# Charger.net
KiCad netlist of a schematic drawn in Altium Designer
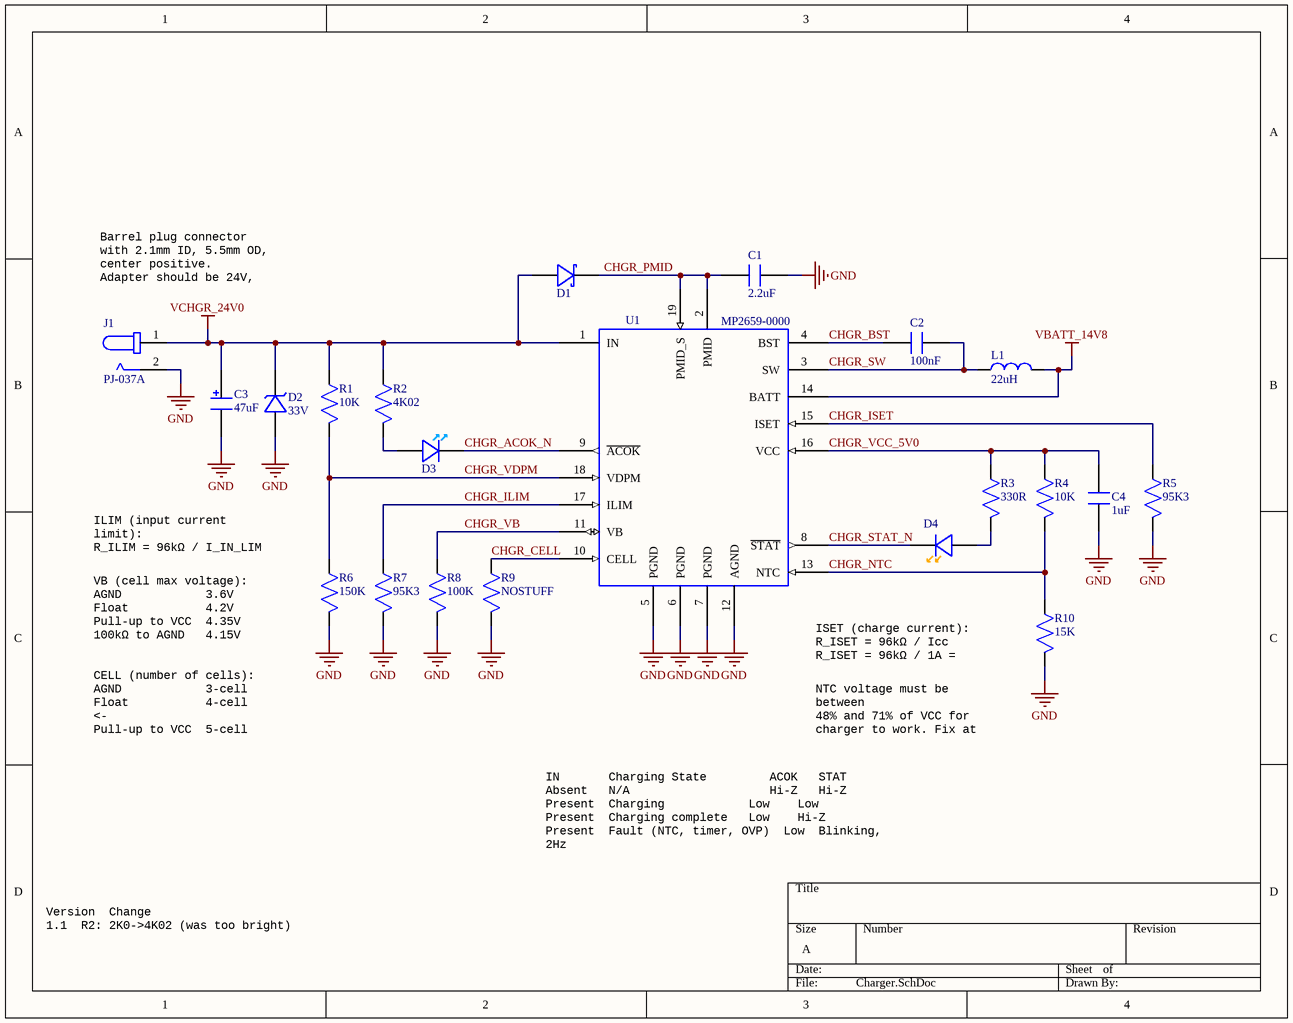
[diagram p0: Charger.SchDoc]

(export (version "E")
  (design (tool "Eeschema 10.0.6"))
  (components
    (comp (ref "C1")
      (value "~")
      (footprint "1206_CAP")
      (fields
        (field (name "MANUFACTURER") "Samsung Electro-Mechanics")
        (field (name "PART NUMBER") "CL31B225KBHNFNE")
        (field (name "TOLERANCE") "10%")
        (field (name "CAPACITANCE") "2.2uF")
      )
      (libsource (lib "SharedPartsLib") (part "CAP_1206_2.2uF"))
    )
    (comp (ref "C2")
      (value "~")
      (footprint "0603_CAP")
      (fields
        (field (name "MANUFACTURER") "Samsung Electro-Mechanics")
        (field (name "PART NUMBER") "CL10B104KB8NNWC")
        (field (name "TOLERANCE") "10%")
        (field (name "CAPACITANCE") "100nF")
      )
      (libsource (lib "SharedPartsLib") (part "CAP_0603_100nF"))
    )
    (comp (ref "C3")
      (value "~")
      (footprint "CAP_RADIAL_5MMx11MM")
      (fields
        (field (name "MANUFACTURER") "Würth Elektronik")
        (field (name "PART NUMBER") "860020572006")
        (field (name "TOLERANCE") "20%")
        (field (name "CAPACITANCE") "47uF")
      )
      (libsource (lib "SharedPartsLib") (part "CAP_RADIAL_47uF"))
    )
    (comp (ref "C4")
      (value "~")
      (footprint "0603_CAP")
      (fields
        (field (name "MANUFACTURER") "Samsung Electro-Mechanics")
        (field (name "PART NUMBER") "CL10B105KA8NNNC")
        (field (name "TOLERANCE") "10%")
        (field (name "CAPACITANCE") "1uF")
      )
      (libsource (lib "SharedPartsLib") (part "CAP_0603_1uF"))
    )
    (comp (ref "D1")
      (value "*")
      (footprint "DO-214AC_SMA")
      (fields (field (name "MANUFACTURER") "Diodes Incorporated") (field (name "PART NUMBER") "B240AE-13"))
      (libsource (lib "SharedPartsLib") (part "DIODE_SCHOTTKY_40V_2A"))
    )
    (comp (ref "D2")
      (value "*")
      (footprint "DO-214AC_SMA")
      (fields
        (field (name "MANUFACTURER") "Diodes Incorporated")
        (field (name "PART NUMBER") "SMAJ33AQ-13-F")
        (field (name "REVERSE STANDOFF VOLTAGE") "33V")
      )
      (libsource (lib "SharedPartsLib") (part "DIODE_TVS_33V_UNIDIR"))
    )
    (comp (ref "D3")
      (value "*")
      (footprint "LED_1411")
      (fields (field (name "MANUFACTURER") "Würth Elektronik") (field (name "PART NUMBER") "150141BS73100"))
      (libsource (lib "SharedPartsLib") (part "LED_BLUE_150141BS73100"))
    )
    (comp (ref "D4")
      (value "*")
      (footprint "LED_1411")
      (fields (field (name "MANUFACTURER") "Würth Elektronik") (field (name "PART NUMBER") "150141AS73100"))
      (libsource (lib "SharedPartsLib") (part "LED_AMBER_150141AS73100"))
    )
    (comp (ref "J1")
      (value "*")
      (footprint "CONN_BARREL_PLUG_PJ-037A")
      (fields (field (name "MANUFACTURER") "CUI Devices") (field (name "PART NUMBER") "PJ-037A"))
      (libsource (lib "SharedPartsLib") (part "CONN_BARREL_PLUG_PJ-037A"))
    )
    (comp (ref "L1")
      (value "~")
      (footprint "IND_AMRM00101040220MA1")
      (fields
        (field (name "MANUFACTURER") "Pulse Electronics")
        (field (name "PART NUMBER") "AMRM00101040220MA1")
        (field (name "TOLERANCE") "20%")
        (field (name "INDUCTANCE") "22uH")
      )
      (libsource (lib "SharedPartsLib") (part "IND_AMRM00101040220MA1_22U0"))
    )
    (comp (ref "R1")
      (value "~")
      (footprint "0603_RES")
      (fields
        (field (name "MANUFACTURER") "Stackpole Electronics Inc")
        (field (name "PART NUMBER") "RMCF0603FT10K0")
        (field (name "TOLERANCE") "1%")
        (field (name "RESISTANCE") "10K")
      )
      (libsource (lib "SharedPartsLib") (part "RES_0603_10K"))
    )
    (comp (ref "R2")
      (value "~")
      (footprint "0603_RES")
      (fields
        (field (name "MANUFACTURER") "Stackpole Electronics Inc")
        (field (name "PART NUMBER") "RMCF0603FT4K02")
        (field (name "TOLERANCE") "1%")
        (field (name "RESISTANCE") "4K02")
      )
      (libsource (lib "SharedPartsLib") (part "RES_0603_4K02"))
    )
    (comp (ref "R3")
      (value "~")
      (footprint "0603_RES")
      (fields
        (field (name "MANUFACTURER") "Stackpole Electronics Inc")
        (field (name "PART NUMBER") "RMCF0603FT330R")
        (field (name "TOLERANCE") "1%")
        (field (name "RESISTANCE") "330R")
      )
      (libsource (lib "SharedPartsLib") (part "RES_0603_330R"))
    )
    (comp (ref "R4")
      (value "~")
      (footprint "0603_RES")
      (fields
        (field (name "MANUFACTURER") "Stackpole Electronics Inc")
        (field (name "PART NUMBER") "RMCF0603FT10K0")
        (field (name "TOLERANCE") "1%")
        (field (name "RESISTANCE") "10K")
      )
      (libsource (lib "SharedPartsLib") (part "RES_0603_10K"))
    )
    (comp (ref "R5")
      (value "~")
      (footprint "0603_RES")
      (fields
        (field (name "MANUFACTURER") "Stackpole Electronics Inc.")
        (field (name "PART NUMBER") "RMCF0603FT95K3")
        (field (name "TOLERANCE") "1%")
        (field (name "RESISTANCE") "95K3")
      )
      (libsource (lib "SharedPartsLib") (part "RES_0603_95K3"))
    )
    (comp (ref "R6")
      (value "~")
      (footprint "0603_RES")
      (fields
        (field (name "MANUFACTURER") "Stackpole Electronics Inc")
        (field (name "PART NUMBER") "RMCF0603FG150K")
        (field (name "TOLERANCE") "1%")
        (field (name "RESISTANCE") "150K")
      )
      (libsource (lib "SharedPartsLib") (part "RES_0603_150K"))
    )
    (comp (ref "R7")
      (value "~")
      (footprint "0603_RES")
      (fields
        (field (name "MANUFACTURER") "Stackpole Electronics Inc.")
        (field (name "PART NUMBER") "RMCF0603FT95K3")
        (field (name "TOLERANCE") "1%")
        (field (name "RESISTANCE") "95K3")
      )
      (libsource (lib "SharedPartsLib") (part "RES_0603_95K3"))
    )
    (comp (ref "R8")
      (value "~")
      (footprint "0603_RES")
      (fields
        (field (name "MANUFACTURER") "Stackpole")
        (field (name "PART NUMBER") "RMCF0603FT100K")
        (field (name "TOLERANCE") "1%")
        (field (name "RESISTANCE") "100K")
      )
      (libsource (lib "SharedPartsLib") (part "RES_0603_100K"))
    )
    (comp (ref "R9")
      (value "~")
      (footprint "0603_RES")
      (fields (field (name "NOSTUFF") "NOSTUFF"))
      (libsource (lib "SharedPartsLib") (part "RES_0603_NOSTUFF"))
    )
    (comp (ref "R10")
      (value "~")
      (footprint "0603_RES")
      (fields
        (field (name "MANUFACTURER") "Stackpole Electronics Inc")
        (field (name "PART NUMBER") "RMCF0603FG15K0")
        (field (name "TOLERANCE") "1%")
        (field (name "RESISTANCE") "15K")
      )
      (libsource (lib "SharedPartsLib") (part "RES_0603_15K"))
    )
    (comp (ref "U1")
      (value "~")
      (footprint "QFN-19")
      (fields
        (field (name "MANUFACTURER") "Monolithic Power Systems")
        (field (name "PART NUMBER") "MP2659-0000")
      )
      (libsource (lib "SharedPartsLib") (part "MP2659"))
    )
  )
  (nets
    (net (code "1") (name "/CHGR_ACOK_N") (class "Default")
      (node (ref "D3") (pin "1") (pintype "passive"))
      (node (ref "U1") (pin "9") (pinfunction "~{ACOK}_9") (pintype "output"))
    )
    (net (code "2") (name "/CHGR_BST") (class "Default")
      (node (ref "C2") (pin "2") (pintype "passive"))
      (node (ref "U1") (pin "4") (pinfunction "BST_4") (pintype "passive"))
    )
    (net (code "3") (name "/CHGR_CELL") (class "Default")
      (node (ref "R9") (pin "2") (pintype "passive"))
      (node (ref "U1") (pin "10") (pinfunction "CELL_10") (pintype "input"))
    )
    (net (code "4") (name "/CHGR_ILIM") (class "Default")
      (node (ref "R7") (pin "2") (pintype "passive"))
      (node (ref "U1") (pin "17") (pinfunction "ILIM_17") (pintype "input"))
    )
    (net (code "5") (name "/CHGR_ISET") (class "Default")
      (node (ref "R5") (pin "2") (pintype "passive"))
      (node (ref "U1") (pin "15") (pinfunction "ISET_15") (pintype "input"))
    )
    (net (code "6") (name "/CHGR_NTC") (class "Default")
      (node (ref "R10") (pin "2") (pintype "passive"))
      (node (ref "R4") (pin "1") (pintype "passive"))
      (node (ref "U1") (pin "13") (pinfunction "NTC_13") (pintype "input"))
    )
    (net (code "7") (name "/CHGR_PMID") (class "Default")
      (node (ref "C1") (pin "2") (pintype "passive"))
      (node (ref "D1") (pin "1") (pintype "passive"))
      (node (ref "U1") (pin "19") (pinfunction "PMID_S_19") (pintype "input"))
      (node (ref "U1") (pin "2") (pinfunction "PMID_2") (pintype "passive"))
    )
    (net (code "8") (name "/CHGR_STAT_N") (class "Default")
      (node (ref "D4") (pin "1") (pintype "passive"))
      (node (ref "U1") (pin "8") (pinfunction "~{STAT}_8") (pintype "output"))
    )
    (net (code "9") (name "/CHGR_SW") (class "Default")
      (node (ref "C2") (pin "1") (pintype "passive"))
      (node (ref "L1") (pin "1") (pintype "passive"))
      (node (ref "U1") (pin "3") (pinfunction "SW_3") (pintype "passive"))
    )
    (net (code "10") (name "/CHGR_VB") (class "Default")
      (node (ref "R8") (pin "2") (pintype "passive"))
      (node (ref "U1") (pin "11") (pinfunction "VB_11") (pintype "bidirectional"))
    )
    (net (code "11") (name "/CHGR_VCC_5V0") (class "Default")
      (node (ref "C4") (pin "2") (pintype "passive"))
      (node (ref "R3") (pin "2") (pintype "passive"))
      (node (ref "R4") (pin "2") (pintype "passive"))
      (node (ref "U1") (pin "16") (pinfunction "VCC_16") (pintype "input"))
    )
    (net (code "12") (name "/CHGR_VDPM") (class "Default")
      (node (ref "R1") (pin "1") (pintype "passive"))
      (node (ref "R6") (pin "2") (pintype "passive"))
      (node (ref "U1") (pin "18") (pinfunction "VDPM_18") (pintype "input"))
    )
    (net (code "13") (name "GND") (class "Default")
      (node (ref "C1") (pin "1") (pintype "passive"))
      (node (ref "C3") (pin "2") (pintype "passive"))
      (node (ref "C4") (pin "1") (pintype "passive"))
      (node (ref "D2") (pin "2") (pintype "passive"))
      (node (ref "J1") (pin "2") (pinfunction "2_2") (pintype "passive"))
      (node (ref "R10") (pin "1") (pintype "passive"))
      (node (ref "R5") (pin "1") (pintype "passive"))
      (node (ref "R6") (pin "1") (pintype "passive"))
      (node (ref "R7") (pin "1") (pintype "passive"))
      (node (ref "R8") (pin "1") (pintype "passive"))
      (node (ref "R9") (pin "1") (pintype "passive"))
      (node (ref "U1") (pin "12") (pinfunction "AGND_12") (pintype "passive"))
      (node (ref "U1") (pin "5") (pinfunction "PGND_5") (pintype "passive"))
      (node (ref "U1") (pin "6") (pinfunction "PGND_6") (pintype "passive"))
      (node (ref "U1") (pin "7") (pinfunction "PGND_7") (pintype "passive"))
    )
    (net (code "14") (name "Net-(D3-Pad2)") (class "Default")
      (node (ref "D3") (pin "2") (pintype "passive"))
      (node (ref "R2") (pin "1") (pintype "passive"))
    )
    (net (code "15") (name "Net-(D4-Pad2)") (class "Default")
      (node (ref "D4") (pin "2") (pintype "passive"))
      (node (ref "R3") (pin "1") (pintype "passive"))
    )
    (net (code "16") (name "VBATT_14V8") (class "Default")
      (node (ref "L1") (pin "2") (pintype "passive"))
      (node (ref "U1") (pin "14") (pinfunction "BATT_14") (pintype "passive"))
    )
    (net (code "17") (name "VCHGR_24V0") (class "Default")
      (node (ref "C3") (pin "1") (pintype "passive"))
      (node (ref "D1") (pin "2") (pintype "passive"))
      (node (ref "D2") (pin "1") (pintype "passive"))
      (node (ref "J1") (pin "1") (pinfunction "1_1") (pintype "passive"))
      (node (ref "R1") (pin "2") (pintype "passive"))
      (node (ref "R2") (pin "2") (pintype "passive"))
      (node (ref "U1") (pin "1") (pinfunction "IN_1") (pintype "passive"))
    )
  )
)
